# SparkFun_IMU_Breakout_ICM-20948_FET_EVAL.net
KiCad netlist of a schematic drawn in EAGLE
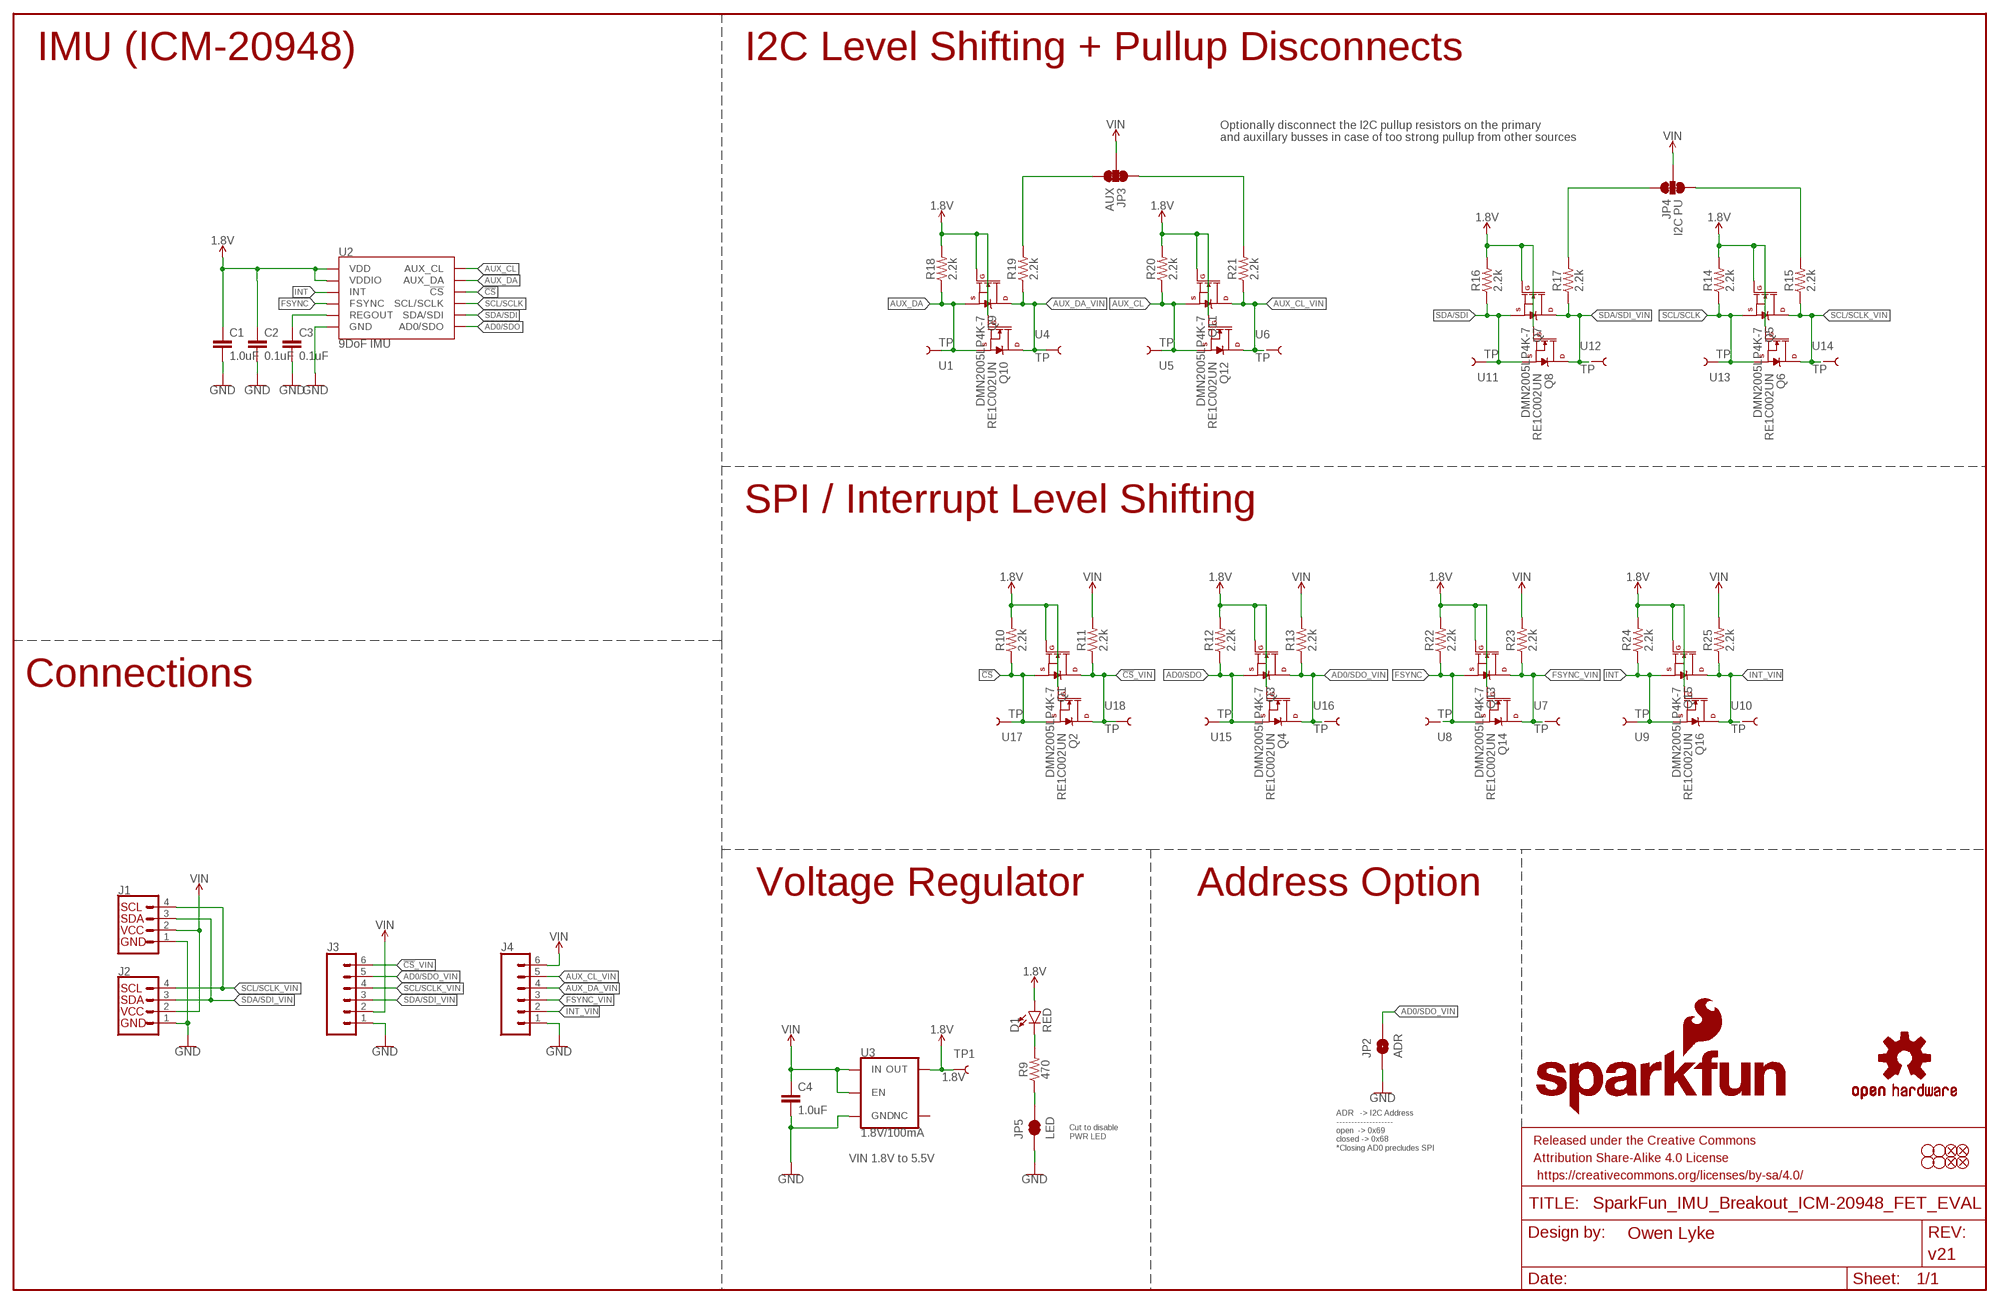
[diagram p0: schematic, sheet 1]

(export (version "E")
  (design (tool "Eeschema 10.0.6"))
  (components
    (comp (ref "C1")
      (value "1.0uF")
      (footprint "eagle-import:0603")
      (libsource (lib "eagle-import") (part "1.0UF-0603-16V-10%-X7R"))
    )
    (comp (ref "C2")
      (value "0.1uF")
      (footprint "eagle-import:0603")
      (libsource (lib "eagle-import") (part "0.1UF-0603-25V-5%"))
    )
    (comp (ref "C3")
      (value "0.1uF")
      (footprint "eagle-import:0603")
      (libsource (lib "eagle-import") (part "0.1UF-0603-25V-5%"))
    )
    (comp (ref "C4")
      (value "1.0uF")
      (footprint "eagle-import:0603")
      (libsource (lib "eagle-import") (part "1.0UF-0603-16V-10%-X7R"))
    )
    (comp (ref "D1")
      (value "RED")
      (footprint "eagle-import:LED-0603")
      (libsource (lib "eagle-import") (part "LED-RED0603"))
    )
    (comp (ref "FD1")
      (value "FIDUCIAL1X2")
      (footprint "eagle-import:FIDUCIAL-1X2")
      (libsource (lib "eagle-import") (part "FIDUCIAL1X2"))
    )
    (comp (ref "FD2")
      (value "FIDUCIAL1X2")
      (footprint "eagle-import:FIDUCIAL-1X2")
      (libsource (lib "eagle-import") (part "FIDUCIAL1X2"))
    )
    (comp (ref "FD3")
      (value "FIDUCIAL1X2")
      (footprint "eagle-import:FIDUCIAL-1X2")
      (libsource (lib "eagle-import") (part "FIDUCIAL1X2"))
    )
    (comp (ref "FD4")
      (value "FIDUCIAL1X2")
      (footprint "eagle-import:FIDUCIAL-1X2")
      (libsource (lib "eagle-import") (part "FIDUCIAL1X2"))
    )
    (comp (ref "FRAME2")
      (value "FRAME-LEDGER")
      (footprint "eagle-import:CREATIVE_COMMONS")
      (fields (field (name "DESIGNER") "Owen Lyke") (field (name "REV") "v21"))
      (libsource (lib "eagle-import") (part "FRAME-LEDGER"))
    )
    (comp (ref "H1")
      (value "STAND-OFF")
      (footprint "eagle-import:STAND-OFF")
      (libsource (lib "eagle-import") (part "STAND-OFF"))
    )
    (comp (ref "H2")
      (value "STAND-OFF")
      (footprint "eagle-import:STAND-OFF")
      (libsource (lib "eagle-import") (part "STAND-OFF"))
    )
    (comp (ref "H3")
      (value "STAND-OFF")
      (footprint "eagle-import:STAND-OFF")
      (libsource (lib "eagle-import") (part "STAND-OFF"))
    )
    (comp (ref "H4")
      (value "STAND-OFF")
      (footprint "eagle-import:STAND-OFF")
      (libsource (lib "eagle-import") (part "STAND-OFF"))
    )
    (comp (ref "J1")
      (value "QWIIC_CONNECTORJS-1MM")
      (footprint "eagle-import:JST04_1MM_RA")
      (libsource (lib "eagle-import") (part "QWIIC_CONNECTORJS-1MM"))
    )
    (comp (ref "J2")
      (value "QWIIC_CONNECTORJS-1MM")
      (footprint "eagle-import:JST04_1MM_RA")
      (libsource (lib "eagle-import") (part "QWIIC_CONNECTORJS-1MM"))
    )
    (comp (ref "J3")
      (value "CONN_06NO_SILK_NO_POP")
      (footprint "eagle-import:1X06_NO_SILK")
      (libsource (lib "eagle-import") (part "CONN_06NO_SILK_NO_POP"))
    )
    (comp (ref "J4")
      (value "CONN_06NO_SILK_NO_POP")
      (footprint "eagle-import:1X06_NO_SILK")
      (libsource (lib "eagle-import") (part "CONN_06NO_SILK_NO_POP"))
    )
    (comp (ref "JP2")
      (value "ADR")
      (footprint "eagle-import:SMT-JUMPER_2_NO_SILK")
      (libsource (lib "eagle-import") (part "JUMPER-SMT_2_NO_SILK"))
    )
    (comp (ref "JP3")
      (value "AUX")
      (footprint "eagle-import:SMT-JUMPER_3_2-NC_TRACE_SILK")
      (libsource (lib "eagle-import") (part "JUMPER-SMT_3_2-NC_TRACE_SILK"))
    )
    (comp (ref "JP4")
      (value "I2C PU")
      (footprint "eagle-import:SMT-JUMPER_3_2-NC_TRACE_SILK")
      (libsource (lib "eagle-import") (part "JUMPER-SMT_3_2-NC_TRACE_SILK"))
    )
    (comp (ref "JP5")
      (value "LED")
      (footprint "eagle-import:SMT-JUMPER_2_NC_TRACE_SILK")
      (libsource (lib "eagle-import") (part "JUMPER-SMT_2_NC_TRACE_SILK"))
    )
    (comp (ref "LOGO1")
      (value "SFE_LOGO_NAME_FLAME.1_INCH")
      (footprint "eagle-import:SFE_LOGO_NAME_FLAME_.1")
      (libsource (lib "eagle-import") (part "SFE_LOGO_NAME_FLAME.1_INCH"))
    )
    (comp (ref "LOGO2")
      (value "OSHW-LOGOMINI")
      (footprint "eagle-import:OSHW-LOGO-MINI")
      (libsource (lib "eagle-import") (part "OSHW-LOGOMINI"))
    )
    (comp (ref "Q1")
      (value "DMN2005LP4K-7")
      (footprint "eagle-import:AP02001")
      (libsource (lib "eagle-import") (part "DMN2005LP4K-7"))
    )
    (comp (ref "Q2")
      (value "RE1C002UN")
      (footprint "eagle-import:SOT-416FL")
      (libsource (lib "eagle-import") (part "RE1C002UN"))
    )
    (comp (ref "Q3")
      (value "DMN2005LP4K-7")
      (footprint "eagle-import:AP02001")
      (libsource (lib "eagle-import") (part "DMN2005LP4K-7"))
    )
    (comp (ref "Q4")
      (value "RE1C002UN")
      (footprint "eagle-import:SOT-416FL")
      (libsource (lib "eagle-import") (part "RE1C002UN"))
    )
    (comp (ref "Q5")
      (value "DMN2005LP4K-7")
      (footprint "eagle-import:AP02001")
      (libsource (lib "eagle-import") (part "DMN2005LP4K-7"))
    )
    (comp (ref "Q6")
      (value "RE1C002UN")
      (footprint "eagle-import:SOT-416FL")
      (libsource (lib "eagle-import") (part "RE1C002UN"))
    )
    (comp (ref "Q7")
      (value "DMN2005LP4K-7")
      (footprint "eagle-import:AP02001")
      (libsource (lib "eagle-import") (part "DMN2005LP4K-7"))
    )
    (comp (ref "Q8")
      (value "RE1C002UN")
      (footprint "eagle-import:SOT-416FL")
      (libsource (lib "eagle-import") (part "RE1C002UN"))
    )
    (comp (ref "Q9")
      (value "DMN2005LP4K-7")
      (footprint "eagle-import:AP02001")
      (libsource (lib "eagle-import") (part "DMN2005LP4K-7"))
    )
    (comp (ref "Q10")
      (value "RE1C002UN")
      (footprint "eagle-import:SOT-416FL")
      (libsource (lib "eagle-import") (part "RE1C002UN"))
    )
    (comp (ref "Q11")
      (value "DMN2005LP4K-7")
      (footprint "eagle-import:AP02001")
      (libsource (lib "eagle-import") (part "DMN2005LP4K-7"))
    )
    (comp (ref "Q12")
      (value "RE1C002UN")
      (footprint "eagle-import:SOT-416FL")
      (libsource (lib "eagle-import") (part "RE1C002UN"))
    )
    (comp (ref "Q13")
      (value "DMN2005LP4K-7")
      (footprint "eagle-import:AP02001")
      (libsource (lib "eagle-import") (part "DMN2005LP4K-7"))
    )
    (comp (ref "Q14")
      (value "RE1C002UN")
      (footprint "eagle-import:SOT-416FL")
      (libsource (lib "eagle-import") (part "RE1C002UN"))
    )
    (comp (ref "Q15")
      (value "DMN2005LP4K-7")
      (footprint "eagle-import:AP02001")
      (libsource (lib "eagle-import") (part "DMN2005LP4K-7"))
    )
    (comp (ref "Q16")
      (value "RE1C002UN")
      (footprint "eagle-import:SOT-416FL")
      (libsource (lib "eagle-import") (part "RE1C002UN"))
    )
    (comp (ref "R9")
      (value "470")
      (footprint "eagle-import:0603")
      (libsource (lib "eagle-import") (part "470OHM-0603-1/10W-1%"))
    )
    (comp (ref "R10")
      (value "2.2k")
      (footprint "eagle-import:0402-TIGHT")
      (libsource (lib "eagle-import") (part "2.2KOHM-0402T-1/16W-1%"))
    )
    (comp (ref "R11")
      (value "2.2k")
      (footprint "eagle-import:0402-TIGHT")
      (libsource (lib "eagle-import") (part "2.2KOHM-0402T-1/16W-1%"))
    )
    (comp (ref "R12")
      (value "2.2k")
      (footprint "eagle-import:0402-TIGHT")
      (libsource (lib "eagle-import") (part "2.2KOHM-0402T-1/16W-1%"))
    )
    (comp (ref "R13")
      (value "2.2k")
      (footprint "eagle-import:0402-TIGHT")
      (libsource (lib "eagle-import") (part "2.2KOHM-0402T-1/16W-1%"))
    )
    (comp (ref "R14")
      (value "2.2k")
      (footprint "eagle-import:0402-TIGHT")
      (libsource (lib "eagle-import") (part "2.2KOHM-0402T-1/16W-1%"))
    )
    (comp (ref "R15")
      (value "2.2k")
      (footprint "eagle-import:0402-TIGHT")
      (libsource (lib "eagle-import") (part "2.2KOHM-0402T-1/16W-1%"))
    )
    (comp (ref "R16")
      (value "2.2k")
      (footprint "eagle-import:0402-TIGHT")
      (libsource (lib "eagle-import") (part "2.2KOHM-0402T-1/16W-1%"))
    )
    (comp (ref "R17")
      (value "2.2k")
      (footprint "eagle-import:0402-TIGHT")
      (libsource (lib "eagle-import") (part "2.2KOHM-0402T-1/16W-1%"))
    )
    (comp (ref "R18")
      (value "2.2k")
      (footprint "eagle-import:0402-TIGHT")
      (libsource (lib "eagle-import") (part "2.2KOHM-0402T-1/16W-1%"))
    )
    (comp (ref "R19")
      (value "2.2k")
      (footprint "eagle-import:0402-TIGHT")
      (libsource (lib "eagle-import") (part "2.2KOHM-0402T-1/16W-1%"))
    )
    (comp (ref "R20")
      (value "2.2k")
      (footprint "eagle-import:0402-TIGHT")
      (libsource (lib "eagle-import") (part "2.2KOHM-0402T-1/16W-1%"))
    )
    (comp (ref "R21")
      (value "2.2k")
      (footprint "eagle-import:0402-TIGHT")
      (libsource (lib "eagle-import") (part "2.2KOHM-0402T-1/16W-1%"))
    )
    (comp (ref "R22")
      (value "2.2k")
      (footprint "eagle-import:0402-TIGHT")
      (libsource (lib "eagle-import") (part "2.2KOHM-0402T-1/16W-1%"))
    )
    (comp (ref "R23")
      (value "2.2k")
      (footprint "eagle-import:0402-TIGHT")
      (libsource (lib "eagle-import") (part "2.2KOHM-0402T-1/16W-1%"))
    )
    (comp (ref "R24")
      (value "2.2k")
      (footprint "eagle-import:0402-TIGHT")
      (libsource (lib "eagle-import") (part "2.2KOHM-0402T-1/16W-1%"))
    )
    (comp (ref "R25")
      (value "2.2k")
      (footprint "eagle-import:0402-TIGHT")
      (libsource (lib "eagle-import") (part "2.2KOHM-0402T-1/16W-1%"))
    )
    (comp (ref "TP1")
      (value "1.8V")
      (footprint "eagle-import:PAD.03X.03")
      (libsource (lib "eagle-import") (part "TEST-POINT3"))
    )
    (comp (ref "U1")
      (value "TP")
      (footprint "eagle-import:MINI_TEST_POINT")
      (libsource (lib "eagle-import") (part "TP"))
    )
    (comp (ref "U2")
      (value "9DoF IMU")
      (footprint "eagle-import:QFN24-3X3")
      (libsource (lib "eagle-import") (part "ICM-20948"))
    )
    (comp (ref "U3")
      (value "1.8V/100mA")
      (footprint "eagle-import:SC70")
      (libsource (lib "eagle-import") (part "V_REG_SP6214-1.8V"))
    )
    (comp (ref "U4")
      (value "TP")
      (footprint "eagle-import:MINI_TEST_POINT")
      (libsource (lib "eagle-import") (part "TP"))
    )
    (comp (ref "U5")
      (value "TP")
      (footprint "eagle-import:MINI_TEST_POINT")
      (libsource (lib "eagle-import") (part "TP"))
    )
    (comp (ref "U6")
      (value "TP")
      (footprint "eagle-import:MINI_TEST_POINT")
      (libsource (lib "eagle-import") (part "TP"))
    )
    (comp (ref "U7")
      (value "TP")
      (footprint "eagle-import:MINI_TEST_POINT")
      (libsource (lib "eagle-import") (part "TP"))
    )
    (comp (ref "U8")
      (value "TP")
      (footprint "eagle-import:MINI_TEST_POINT")
      (libsource (lib "eagle-import") (part "TP"))
    )
    (comp (ref "U9")
      (value "TP")
      (footprint "eagle-import:MINI_TEST_POINT")
      (libsource (lib "eagle-import") (part "TP"))
    )
    (comp (ref "U10")
      (value "TP")
      (footprint "eagle-import:MINI_TEST_POINT")
      (libsource (lib "eagle-import") (part "TP"))
    )
    (comp (ref "U11")
      (value "TP")
      (footprint "eagle-import:MINI_TEST_POINT")
      (libsource (lib "eagle-import") (part "TP"))
    )
    (comp (ref "U12")
      (value "TP")
      (footprint "eagle-import:MINI_TEST_POINT")
      (libsource (lib "eagle-import") (part "TP"))
    )
    (comp (ref "U13")
      (value "TP")
      (footprint "eagle-import:MINI_TEST_POINT")
      (libsource (lib "eagle-import") (part "TP"))
    )
    (comp (ref "U14")
      (value "TP")
      (footprint "eagle-import:MINI_TEST_POINT")
      (libsource (lib "eagle-import") (part "TP"))
    )
    (comp (ref "U15")
      (value "TP")
      (footprint "eagle-import:MINI_TEST_POINT")
      (libsource (lib "eagle-import") (part "TP"))
    )
    (comp (ref "U16")
      (value "TP")
      (footprint "eagle-import:MINI_TEST_POINT")
      (libsource (lib "eagle-import") (part "TP"))
    )
    (comp (ref "U17")
      (value "TP")
      (footprint "eagle-import:MINI_TEST_POINT")
      (libsource (lib "eagle-import") (part "TP"))
    )
    (comp (ref "U18")
      (value "TP")
      (footprint "eagle-import:MINI_TEST_POINT")
      (libsource (lib "eagle-import") (part "TP"))
    )
  )
  (nets
    (net (code "1") (name "/~{CS}") (class "Default")
      (node (ref "Q1") (pin "S") (pinfunction "S_S") (pintype "bidirectional"))
      (node (ref "Q2") (pin "2") (pinfunction "S_2") (pintype "bidirectional"))
      (node (ref "R10") (pin "1") (pinfunction "1_1") (pintype "passive"))
      (node (ref "U17") (pin "P$1") (pinfunction "1_P$1") (pintype "bidirectional"))
      (node (ref "U2") (pin "22") (pinfunction "~{CS}_22") (pintype "bidirectional"))
    )
    (net (code "2") (name "/~{CS}_VIN") (class "Default")
      (node (ref "J3") (pin "6") (pinfunction "6_6") (pintype "passive"))
      (node (ref "Q1") (pin "D") (pinfunction "D_D") (pintype "bidirectional"))
      (node (ref "Q2") (pin "3") (pinfunction "D_3") (pintype "bidirectional"))
      (node (ref "R11") (pin "1") (pinfunction "1_1") (pintype "passive"))
      (node (ref "U18") (pin "P$1") (pinfunction "1_P$1") (pintype "bidirectional"))
    )
    (net (code "3") (name "1.8V") (class "Default")
      (node (ref "C1") (pin "1") (pinfunction "1_1") (pintype "passive"))
      (node (ref "C2") (pin "1") (pinfunction "1_1") (pintype "passive"))
      (node (ref "D1") (pin "A") (pinfunction "A_A") (pintype "passive"))
      (node (ref "Q1") (pin "G") (pinfunction "G_G") (pintype "bidirectional"))
      (node (ref "Q10") (pin "1") (pinfunction "G_1") (pintype "bidirectional"))
      (node (ref "Q11") (pin "G") (pinfunction "G_G") (pintype "bidirectional"))
      (node (ref "Q12") (pin "1") (pinfunction "G_1") (pintype "bidirectional"))
      (node (ref "Q13") (pin "G") (pinfunction "G_G") (pintype "bidirectional"))
      (node (ref "Q14") (pin "1") (pinfunction "G_1") (pintype "bidirectional"))
      (node (ref "Q15") (pin "G") (pinfunction "G_G") (pintype "bidirectional"))
      (node (ref "Q16") (pin "1") (pinfunction "G_1") (pintype "bidirectional"))
      (node (ref "Q2") (pin "1") (pinfunction "G_1") (pintype "bidirectional"))
      (node (ref "Q3") (pin "G") (pinfunction "G_G") (pintype "bidirectional"))
      (node (ref "Q4") (pin "1") (pinfunction "G_1") (pintype "bidirectional"))
      (node (ref "Q5") (pin "G") (pinfunction "G_G") (pintype "bidirectional"))
      (node (ref "Q6") (pin "1") (pinfunction "G_1") (pintype "bidirectional"))
      (node (ref "Q7") (pin "G") (pinfunction "G_G") (pintype "bidirectional"))
      (node (ref "Q8") (pin "1") (pinfunction "G_1") (pintype "bidirectional"))
      (node (ref "Q9") (pin "G") (pinfunction "G_G") (pintype "bidirectional"))
      (node (ref "R10") (pin "2") (pinfunction "2_2") (pintype "passive"))
      (node (ref "R12") (pin "2") (pinfunction "2_2") (pintype "passive"))
      (node (ref "R14") (pin "2") (pinfunction "2_2") (pintype "passive"))
      (node (ref "R16") (pin "2") (pinfunction "2_2") (pintype "passive"))
      (node (ref "R18") (pin "2") (pinfunction "2_2") (pintype "passive"))
      (node (ref "R20") (pin "2") (pinfunction "2_2") (pintype "passive"))
      (node (ref "R22") (pin "2") (pinfunction "2_2") (pintype "passive"))
      (node (ref "R24") (pin "2") (pinfunction "2_2") (pintype "passive"))
      (node (ref "TP1") (pin "P$1") (pinfunction "1_P$1") (pintype "bidirectional"))
      (node (ref "U2") (pin "13") (pinfunction "VDD_13") (pintype "bidirectional"))
      (node (ref "U2") (pin "8") (pinfunction "VDDIO_8") (pintype "bidirectional"))
      (node (ref "U3") (pin "5") (pinfunction "OUT_5") (pintype "passive"))
    )
    (net (code "4") (name "AD0{slash}SDO") (class "Default")
      (node (ref "Q3") (pin "S") (pinfunction "S_S") (pintype "bidirectional"))
      (node (ref "Q4") (pin "2") (pinfunction "S_2") (pintype "bidirectional"))
      (node (ref "R12") (pin "1") (pinfunction "1_1") (pintype "passive"))
      (node (ref "U15") (pin "P$1") (pinfunction "1_P$1") (pintype "bidirectional"))
      (node (ref "U2") (pin "9") (pinfunction "AD0/SDO_9") (pintype "bidirectional"))
    )
    (net (code "5") (name "AD0{slash}SDO_VIN") (class "Default")
      (node (ref "J3") (pin "5") (pinfunction "5_5") (pintype "passive"))
      (node (ref "JP2") (pin "2") (pinfunction "2_2") (pintype "passive"))
      (node (ref "Q3") (pin "D") (pinfunction "D_D") (pintype "bidirectional"))
      (node (ref "Q4") (pin "3") (pinfunction "D_3") (pintype "bidirectional"))
      (node (ref "R13") (pin "1") (pinfunction "1_1") (pintype "passive"))
      (node (ref "U16") (pin "P$1") (pinfunction "1_P$1") (pintype "bidirectional"))
    )
    (net (code "6") (name "AUX_CL") (class "Default")
      (node (ref "Q11") (pin "S") (pinfunction "S_S") (pintype "bidirectional"))
      (node (ref "Q12") (pin "2") (pinfunction "S_2") (pintype "bidirectional"))
      (node (ref "R20") (pin "1") (pinfunction "1_1") (pintype "passive"))
      (node (ref "U2") (pin "7") (pinfunction "AUX_CL_7") (pintype "bidirectional"))
      (node (ref "U5") (pin "P$1") (pinfunction "1_P$1") (pintype "bidirectional"))
    )
    (net (code "7") (name "AUX_CL_VIN") (class "Default")
      (node (ref "J4") (pin "5") (pinfunction "5_5") (pintype "passive"))
      (node (ref "Q11") (pin "D") (pinfunction "D_D") (pintype "bidirectional"))
      (node (ref "Q12") (pin "3") (pinfunction "D_3") (pintype "bidirectional"))
      (node (ref "R21") (pin "1") (pinfunction "1_1") (pintype "passive"))
      (node (ref "U6") (pin "P$1") (pinfunction "1_P$1") (pintype "bidirectional"))
    )
    (net (code "8") (name "AUX_DA") (class "Default")
      (node (ref "Q10") (pin "2") (pinfunction "S_2") (pintype "bidirectional"))
      (node (ref "Q9") (pin "S") (pinfunction "S_S") (pintype "bidirectional"))
      (node (ref "R18") (pin "1") (pinfunction "1_1") (pintype "passive"))
      (node (ref "U1") (pin "P$1") (pinfunction "1_P$1") (pintype "bidirectional"))
      (node (ref "U2") (pin "21") (pinfunction "AUX_DA_21") (pintype "bidirectional"))
    )
    (net (code "9") (name "AUX_DA_VIN") (class "Default")
      (node (ref "J4") (pin "4") (pinfunction "4_4") (pintype "passive"))
      (node (ref "Q10") (pin "3") (pinfunction "D_3") (pintype "bidirectional"))
      (node (ref "Q9") (pin "D") (pinfunction "D_D") (pintype "bidirectional"))
      (node (ref "R19") (pin "1") (pinfunction "1_1") (pintype "passive"))
      (node (ref "U4") (pin "P$1") (pinfunction "1_P$1") (pintype "bidirectional"))
    )
    (net (code "10") (name "FSYNC") (class "Default")
      (node (ref "Q13") (pin "S") (pinfunction "S_S") (pintype "bidirectional"))
      (node (ref "Q14") (pin "2") (pinfunction "S_2") (pintype "bidirectional"))
      (node (ref "R22") (pin "1") (pinfunction "1_1") (pintype "passive"))
      (node (ref "U2") (pin "11") (pinfunction "FSYNC_11") (pintype "bidirectional"))
      (node (ref "U8") (pin "P$1") (pinfunction "1_P$1") (pintype "bidirectional"))
    )
    (net (code "11") (name "FSYNC_VIN") (class "Default")
      (node (ref "J4") (pin "3") (pinfunction "3_3") (pintype "passive"))
      (node (ref "Q13") (pin "D") (pinfunction "D_D") (pintype "bidirectional"))
      (node (ref "Q14") (pin "3") (pinfunction "D_3") (pintype "bidirectional"))
      (node (ref "R23") (pin "1") (pinfunction "1_1") (pintype "passive"))
      (node (ref "U7") (pin "P$1") (pinfunction "1_P$1") (pintype "bidirectional"))
    )
    (net (code "12") (name "GND") (class "Default")
      (node (ref "C1") (pin "2") (pinfunction "2_2") (pintype "passive"))
      (node (ref "C2") (pin "2") (pinfunction "2_2") (pintype "passive"))
      (node (ref "C3") (pin "2") (pinfunction "2_2") (pintype "passive"))
      (node (ref "C4") (pin "2") (pinfunction "2_2") (pintype "passive"))
      (node (ref "J1") (pin "1") (pinfunction "1_1") (pintype "power_in"))
      (node (ref "J2") (pin "1") (pinfunction "1_1") (pintype "power_in"))
      (node (ref "J3") (pin "1") (pinfunction "1_1") (pintype "passive"))
      (node (ref "J4") (pin "1") (pinfunction "1_1") (pintype "passive"))
      (node (ref "JP2") (pin "1") (pinfunction "1_1") (pintype "passive"))
      (node (ref "JP5") (pin "1") (pinfunction "1_1") (pintype "passive"))
      (node (ref "U2") (pin "18") (pinfunction "GND_18") (pintype "bidirectional"))
      (node (ref "U2") (pin "20") (pinfunction "GND_20") (pintype "bidirectional"))
      (node (ref "U3") (pin "2") (pinfunction "GND_2") (pintype "input"))
    )
    (net (code "13") (name "INT") (class "Default")
      (node (ref "Q15") (pin "S") (pinfunction "S_S") (pintype "bidirectional"))
      (node (ref "Q16") (pin "2") (pinfunction "S_2") (pintype "bidirectional"))
      (node (ref "R24") (pin "1") (pinfunction "1_1") (pintype "passive"))
      (node (ref "U2") (pin "12") (pinfunction "INT_12") (pintype "bidirectional"))
      (node (ref "U9") (pin "P$1") (pinfunction "1_P$1") (pintype "bidirectional"))
    )
    (net (code "14") (name "INT_VIN") (class "Default")
      (node (ref "J4") (pin "2") (pinfunction "2_2") (pintype "passive"))
      (node (ref "Q15") (pin "D") (pinfunction "D_D") (pintype "bidirectional"))
      (node (ref "Q16") (pin "3") (pinfunction "D_3") (pintype "bidirectional"))
      (node (ref "R25") (pin "1") (pinfunction "1_1") (pintype "passive"))
      (node (ref "U10") (pin "P$1") (pinfunction "1_P$1") (pintype "bidirectional"))
    )
    (net (code "15") (name "Net-(D1-PadC)") (class "Default")
      (node (ref "D1") (pin "C") (pinfunction "C_C") (pintype "passive"))
      (node (ref "R9") (pin "2") (pinfunction "2_2") (pintype "passive"))
    )
    (net (code "16") (name "Net-(JP3-Pad1)") (class "Default")
      (node (ref "JP3") (pin "1") (pinfunction "1_1") (pintype "passive"))
      (node (ref "R21") (pin "2") (pinfunction "2_2") (pintype "passive"))
    )
    (net (code "17") (name "Net-(JP3-Pad3)") (class "Default")
      (node (ref "JP3") (pin "3") (pinfunction "3_3") (pintype "passive"))
      (node (ref "R19") (pin "2") (pinfunction "2_2") (pintype "passive"))
    )
    (net (code "18") (name "Net-(JP4-Pad1)") (class "Default")
      (node (ref "JP4") (pin "1") (pinfunction "1_1") (pintype "passive"))
      (node (ref "R17") (pin "2") (pinfunction "2_2") (pintype "passive"))
    )
    (net (code "19") (name "Net-(JP4-Pad3)") (class "Default")
      (node (ref "JP4") (pin "3") (pinfunction "3_3") (pintype "passive"))
      (node (ref "R15") (pin "2") (pinfunction "2_2") (pintype "passive"))
    )
    (net (code "20") (name "Net-(JP5-Pad2)") (class "Default")
      (node (ref "JP5") (pin "2") (pinfunction "2_2") (pintype "passive"))
      (node (ref "R9") (pin "1") (pinfunction "1_1") (pintype "passive"))
    )
    (net (code "21") (name "Net-(U2-REGOUT)") (class "Default")
      (node (ref "C3") (pin "1") (pinfunction "1_1") (pintype "passive"))
      (node (ref "U2") (pin "10") (pinfunction "REGOUT_10") (pintype "bidirectional"))
    )
    (net (code "22") (name "SCL{slash}SCLK") (class "Default")
      (node (ref "Q5") (pin "S") (pinfunction "S_S") (pintype "bidirectional"))
      (node (ref "Q6") (pin "2") (pinfunction "S_2") (pintype "bidirectional"))
      (node (ref "R14") (pin "1") (pinfunction "1_1") (pintype "passive"))
      (node (ref "U13") (pin "P$1") (pinfunction "1_P$1") (pintype "bidirectional"))
      (node (ref "U2") (pin "23") (pinfunction "SCL/SCLK_23") (pintype "bidirectional"))
    )
    (net (code "23") (name "SCL{slash}SCLK_VIN") (class "Default")
      (node (ref "J1") (pin "4") (pinfunction "4_4") (pintype "passive"))
      (node (ref "J2") (pin "4") (pinfunction "4_4") (pintype "passive"))
      (node (ref "J3") (pin "4") (pinfunction "4_4") (pintype "passive"))
      (node (ref "Q5") (pin "D") (pinfunction "D_D") (pintype "bidirectional"))
      (node (ref "Q6") (pin "3") (pinfunction "D_3") (pintype "bidirectional"))
      (node (ref "R15") (pin "1") (pinfunction "1_1") (pintype "passive"))
      (node (ref "U14") (pin "P$1") (pinfunction "1_P$1") (pintype "bidirectional"))
    )
    (net (code "24") (name "SDA{slash}SDI") (class "Default")
      (node (ref "Q7") (pin "S") (pinfunction "S_S") (pintype "bidirectional"))
      (node (ref "Q8") (pin "2") (pinfunction "S_2") (pintype "bidirectional"))
      (node (ref "R16") (pin "1") (pinfunction "1_1") (pintype "passive"))
      (node (ref "U11") (pin "P$1") (pinfunction "1_P$1") (pintype "bidirectional"))
      (node (ref "U2") (pin "24") (pinfunction "SDA/SDI_24") (pintype "bidirectional"))
    )
    (net (code "25") (name "SDA{slash}SDI_VIN") (class "Default")
      (node (ref "J1") (pin "3") (pinfunction "3_3") (pintype "passive"))
      (node (ref "J2") (pin "3") (pinfunction "3_3") (pintype "passive"))
      (node (ref "J3") (pin "3") (pinfunction "3_3") (pintype "passive"))
      (node (ref "Q7") (pin "D") (pinfunction "D_D") (pintype "bidirectional"))
      (node (ref "Q8") (pin "3") (pinfunction "D_3") (pintype "bidirectional"))
      (node (ref "R17") (pin "1") (pinfunction "1_1") (pintype "passive"))
      (node (ref "U12") (pin "P$1") (pinfunction "1_P$1") (pintype "bidirectional"))
    )
    (net (code "26") (name "VIN") (class "Default")
      (node (ref "C4") (pin "1") (pinfunction "1_1") (pintype "passive"))
      (node (ref "J1") (pin "2") (pinfunction "2_2") (pintype "power_in"))
      (node (ref "J2") (pin "2") (pinfunction "2_2") (pintype "power_in"))
      (node (ref "J3") (pin "2") (pinfunction "2_2") (pintype "passive"))
      (node (ref "J4") (pin "6") (pinfunction "6_6") (pintype "passive"))
      (node (ref "JP3") (pin "2") (pinfunction "2_2") (pintype "passive"))
      (node (ref "JP4") (pin "2") (pinfunction "2_2") (pintype "passive"))
      (node (ref "R11") (pin "2") (pinfunction "2_2") (pintype "passive"))
      (node (ref "R13") (pin "2") (pinfunction "2_2") (pintype "passive"))
      (node (ref "R23") (pin "2") (pinfunction "2_2") (pintype "passive"))
      (node (ref "R25") (pin "2") (pinfunction "2_2") (pintype "passive"))
      (node (ref "U3") (pin "1") (pinfunction "IN_1") (pintype "input"))
      (node (ref "U3") (pin "3") (pinfunction "EN_3") (pintype "input"))
    )
    (net (code "27") (name "unconnected-(U3-NC-Pad4)") (class "Default")
      (node (ref "U3") (pin "4") (pinfunction "NC_4") (pintype "no_connect"))
    )
  )
)
